# alvin_skripsi_v2.net
KiCad netlist of a schematic drawn in EAGLE
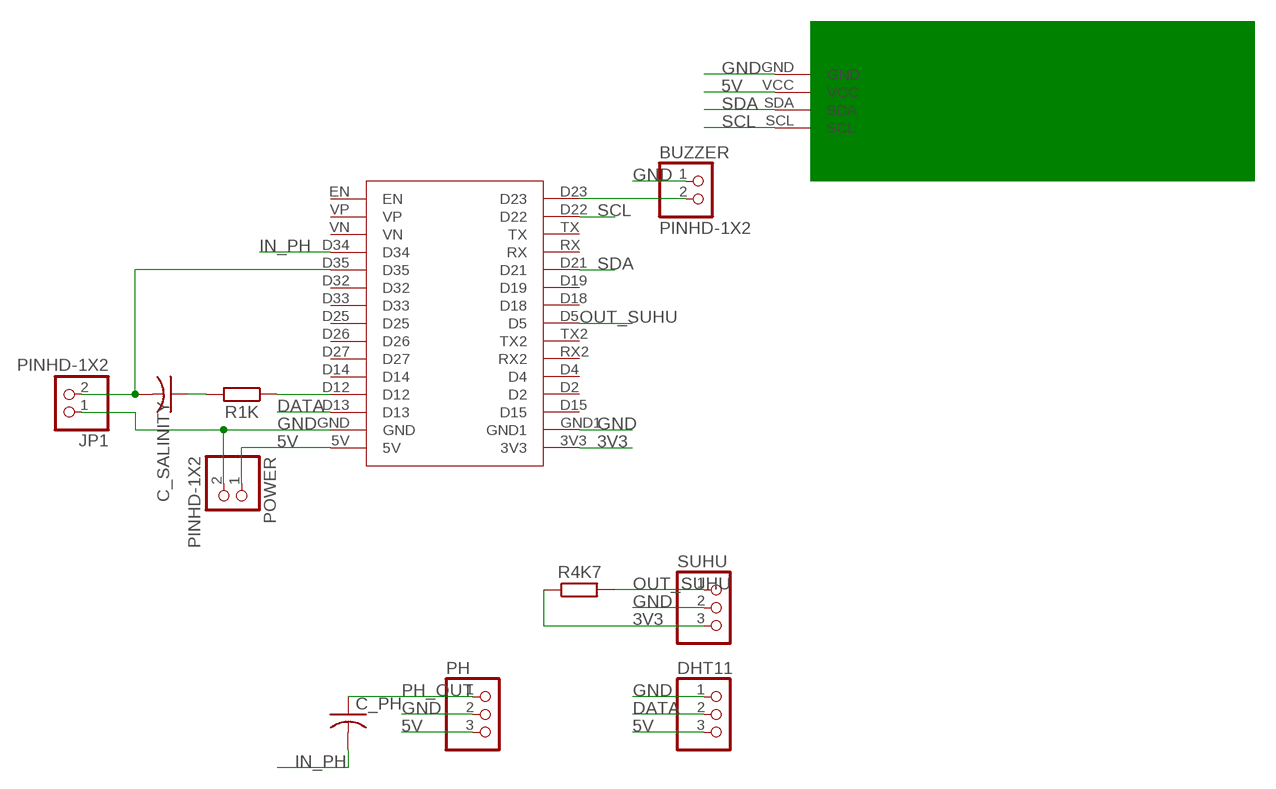
[diagram p0: schematic, sheet 1]

(export (version "E")
  (design (tool "Eeschema 10.0.6"))
  (components
    (comp (ref "BUZZER")
      (value "PINHD-1X2")
      (footprint "eagle-import:1X02")
      (libsource (lib "eagle-import") (part "PINHD-1X2"))
    )
    (comp (ref "C_PH")
      (value "C-US_RADIAL-12.5MM-DIA")
      (footprint "eagle-import:CAPRD550W60D1025H1250B")
      (libsource (lib "eagle-import") (part "C-USRADIAL-12.5MM-DIA_"))
    )
    (comp (ref "C_SALINITY")
      (value "C-US_RADIAL-12.5MM-DIA")
      (footprint "eagle-import:CAPRD550W60D1025H1250B")
      (libsource (lib "eagle-import") (part "C-USRADIAL-12.5MM-DIA_"))
    )
    (comp (ref "DHT11")
      (value "PINHD-1X3CB")
      (footprint "eagle-import:1X03-CLEANBIG")
      (libsource (lib "eagle-import") (part "PINHD-1X3CB"))
    )
    (comp (ref "JP1")
      (value "PINHD-1X2")
      (footprint "eagle-import:1X02")
      (libsource (lib "eagle-import") (part "PINHD-1X2"))
    )
    (comp (ref "PH")
      (value "PINHD-1X3CB")
      (footprint "eagle-import:1X03-CLEANBIG")
      (libsource (lib "eagle-import") (part "PINHD-1X3CB"))
    )
    (comp (ref "POWER")
      (value "PINHD-1X2")
      (footprint "eagle-import:1X02")
      (libsource (lib "eagle-import") (part "PINHD-1X2"))
    )
    (comp (ref "R1K")
      (value "R_AXIAL-7.2MM-PITCH")
      (footprint "eagle-import:RESAD724W46L381D178B")
      (libsource (lib "eagle-import") (part "RAXIAL-7.2MM-PITCH_"))
    )
    (comp (ref "R4K7")
      (value "R_AXIAL-7.2MM-PITCH")
      (footprint "eagle-import:RESAD724W46L381D178B")
      (libsource (lib "eagle-import") (part "RAXIAL-7.2MM-PITCH_"))
    )
    (comp (ref "SUHU")
      (value "PINHD-1X3CB")
      (footprint "eagle-import:1X03-CLEANBIG")
      (libsource (lib "eagle-import") (part "PINHD-1X3CB"))
    )
    (comp (ref "U$1")
      (value "ESP32_30PIN")
      (footprint "eagle-import:ESP32_30PIN")
      (libsource (lib "eagle-import") (part "ESP32_30PIN"))
    )
    (comp (ref "U$2")
      (value "LCD_I2C")
      (footprint "eagle-import:LCD_I2C")
      (libsource (lib "eagle-import") (part "LCD_I2C"))
    )
  )
  (nets
    (net (code "1") (name "/3V3") (class "Default")
      (node (ref "R4K7") (pin "1") (pinfunction "1_1") (pintype "passive"))
      (node (ref "SUHU") (pin "3") (pinfunction "3_3") (pintype "passive"))
      (node (ref "U$1") (pin "3V3") (pinfunction "3V3_3V3") (pintype "bidirectional"))
    )
    (net (code "2") (name "/5V") (class "Default")
      (node (ref "DHT11") (pin "3") (pinfunction "3_3") (pintype "passive"))
      (node (ref "PH") (pin "3") (pinfunction "3_3") (pintype "passive"))
      (node (ref "POWER") (pin "1") (pinfunction "1_1") (pintype "passive"))
      (node (ref "U$1") (pin "5V") (pinfunction "5V_5V") (pintype "bidirectional"))
      (node (ref "U$2") (pin "VCC") (pinfunction "VCC_VCC") (pintype "bidirectional"))
    )
    (net (code "3") (name "/DATA") (class "Default")
      (node (ref "DHT11") (pin "2") (pinfunction "2_2") (pintype "passive"))
      (node (ref "U$1") (pin "D13") (pinfunction "D13_D13") (pintype "bidirectional"))
    )
    (net (code "4") (name "/GND") (class "Default")
      (node (ref "BUZZER") (pin "1") (pinfunction "1_1") (pintype "passive"))
      (node (ref "DHT11") (pin "1") (pinfunction "1_1") (pintype "passive"))
      (node (ref "JP1") (pin "1") (pinfunction "1_1") (pintype "passive"))
      (node (ref "PH") (pin "2") (pinfunction "2_2") (pintype "passive"))
      (node (ref "POWER") (pin "2") (pinfunction "2_2") (pintype "passive"))
      (node (ref "SUHU") (pin "2") (pinfunction "2_2") (pintype "passive"))
      (node (ref "U$1") (pin "GND") (pinfunction "GND_GND") (pintype "bidirectional"))
      (node (ref "U$1") (pin "GND1") (pinfunction "GND1_GND1") (pintype "bidirectional"))
      (node (ref "U$2") (pin "GND") (pinfunction "GND_GND") (pintype "bidirectional"))
    )
    (net (code "5") (name "/IN_PH") (class "Default")
      (node (ref "C_PH") (pin "2") (pinfunction "2_2") (pintype "passive"))
      (node (ref "U$1") (pin "D34") (pinfunction "D34_D34") (pintype "bidirectional"))
    )
    (net (code "6") (name "/OUT_SUHU") (class "Default")
      (node (ref "R4K7") (pin "2") (pinfunction "2_2") (pintype "passive"))
      (node (ref "SUHU") (pin "1") (pinfunction "1_1") (pintype "passive"))
      (node (ref "U$1") (pin "D5") (pinfunction "D5_D5") (pintype "bidirectional"))
    )
    (net (code "7") (name "/PH_OUT") (class "Default")
      (node (ref "C_PH") (pin "1") (pinfunction "1_1") (pintype "passive"))
      (node (ref "PH") (pin "1") (pinfunction "1_1") (pintype "passive"))
    )
    (net (code "8") (name "/SCL") (class "Default")
      (node (ref "U$1") (pin "D22") (pinfunction "D22_D22") (pintype "bidirectional"))
      (node (ref "U$2") (pin "SCL") (pinfunction "SCL_SCL") (pintype "bidirectional"))
    )
    (net (code "9") (name "/SDA") (class "Default")
      (node (ref "U$1") (pin "D21") (pinfunction "D21_D21") (pintype "bidirectional"))
      (node (ref "U$2") (pin "SDA") (pinfunction "SDA_SDA") (pintype "bidirectional"))
    )
    (net (code "10") (name "Net-(BUZZER-Pad2)") (class "Default")
      (node (ref "BUZZER") (pin "2") (pinfunction "2_2") (pintype "passive"))
      (node (ref "U$1") (pin "D23") (pinfunction "D23_D23") (pintype "bidirectional"))
    )
    (net (code "11") (name "Net-(C_SALINITY-Pad1)") (class "Default")
      (node (ref "C_SALINITY") (pin "1") (pinfunction "1_1") (pintype "passive"))
      (node (ref "R1K") (pin "2") (pinfunction "2_2") (pintype "passive"))
    )
    (net (code "12") (name "Net-(C_SALINITY-Pad2)") (class "Default")
      (node (ref "C_SALINITY") (pin "2") (pinfunction "2_2") (pintype "passive"))
      (node (ref "JP1") (pin "2") (pinfunction "2_2") (pintype "passive"))
      (node (ref "U$1") (pin "D35") (pinfunction "D35_D35") (pintype "bidirectional"))
    )
    (net (code "13") (name "Net-(R1K-Pad1)") (class "Default")
      (node (ref "R1K") (pin "1") (pinfunction "1_1") (pintype "passive"))
      (node (ref "U$1") (pin "D12") (pinfunction "D12_D12") (pintype "bidirectional"))
    )
    (net (code "14") (name "unconnected-(U$1-PadD2)") (class "Default")
      (node (ref "U$1") (pin "D2") (pinfunction "D2_D2") (pintype "bidirectional"))
    )
    (net (code "15") (name "unconnected-(U$1-PadD4)") (class "Default")
      (node (ref "U$1") (pin "D4") (pinfunction "D4_D4") (pintype "bidirectional"))
    )
    (net (code "16") (name "unconnected-(U$1-PadD14)") (class "Default")
      (node (ref "U$1") (pin "D14") (pinfunction "D14_D14") (pintype "bidirectional"))
    )
    (net (code "17") (name "unconnected-(U$1-PadD15)") (class "Default")
      (node (ref "U$1") (pin "D15") (pinfunction "D15_D15") (pintype "bidirectional"))
    )
    (net (code "18") (name "unconnected-(U$1-PadD18)") (class "Default")
      (node (ref "U$1") (pin "D18") (pinfunction "D18_D18") (pintype "bidirectional"))
    )
    (net (code "19") (name "unconnected-(U$1-PadD19)") (class "Default")
      (node (ref "U$1") (pin "D19") (pinfunction "D19_D19") (pintype "bidirectional"))
    )
    (net (code "20") (name "unconnected-(U$1-PadD25)") (class "Default")
      (node (ref "U$1") (pin "D25") (pinfunction "D25_D25") (pintype "bidirectional"))
    )
    (net (code "21") (name "unconnected-(U$1-PadD26)") (class "Default")
      (node (ref "U$1") (pin "D26") (pinfunction "D26_D26") (pintype "bidirectional"))
    )
    (net (code "22") (name "unconnected-(U$1-PadD27)") (class "Default")
      (node (ref "U$1") (pin "D27") (pinfunction "D27_D27") (pintype "bidirectional"))
    )
    (net (code "23") (name "unconnected-(U$1-PadD32)") (class "Default")
      (node (ref "U$1") (pin "D32") (pinfunction "D32_D32") (pintype "bidirectional"))
    )
    (net (code "24") (name "unconnected-(U$1-PadD33)") (class "Default")
      (node (ref "U$1") (pin "D33") (pinfunction "D33_D33") (pintype "bidirectional"))
    )
    (net (code "25") (name "unconnected-(U$1-PadEN)") (class "Default")
      (node (ref "U$1") (pin "EN") (pinfunction "EN_EN") (pintype "bidirectional"))
    )
    (net (code "26") (name "unconnected-(U$1-PadRX)") (class "Default")
      (node (ref "U$1") (pin "RX") (pinfunction "RX_RX") (pintype "bidirectional"))
    )
    (net (code "27") (name "unconnected-(U$1-PadRX2)") (class "Default")
      (node (ref "U$1") (pin "RX2") (pinfunction "RX2_RX2") (pintype "bidirectional"))
    )
    (net (code "28") (name "unconnected-(U$1-PadTX)") (class "Default")
      (node (ref "U$1") (pin "TX") (pinfunction "TX_TX") (pintype "bidirectional"))
    )
    (net (code "29") (name "unconnected-(U$1-PadTX2)") (class "Default")
      (node (ref "U$1") (pin "TX2") (pinfunction "TX2_TX2") (pintype "bidirectional"))
    )
    (net (code "30") (name "unconnected-(U$1-PadVN)") (class "Default")
      (node (ref "U$1") (pin "VN") (pinfunction "VN_VN") (pintype "bidirectional"))
    )
    (net (code "31") (name "unconnected-(U$1-PadVP)") (class "Default")
      (node (ref "U$1") (pin "VP") (pinfunction "VP_VP") (pintype "bidirectional"))
    )
  )
)
